# Xbee.net
KiCad netlist of a schematic drawn in Altium Designer
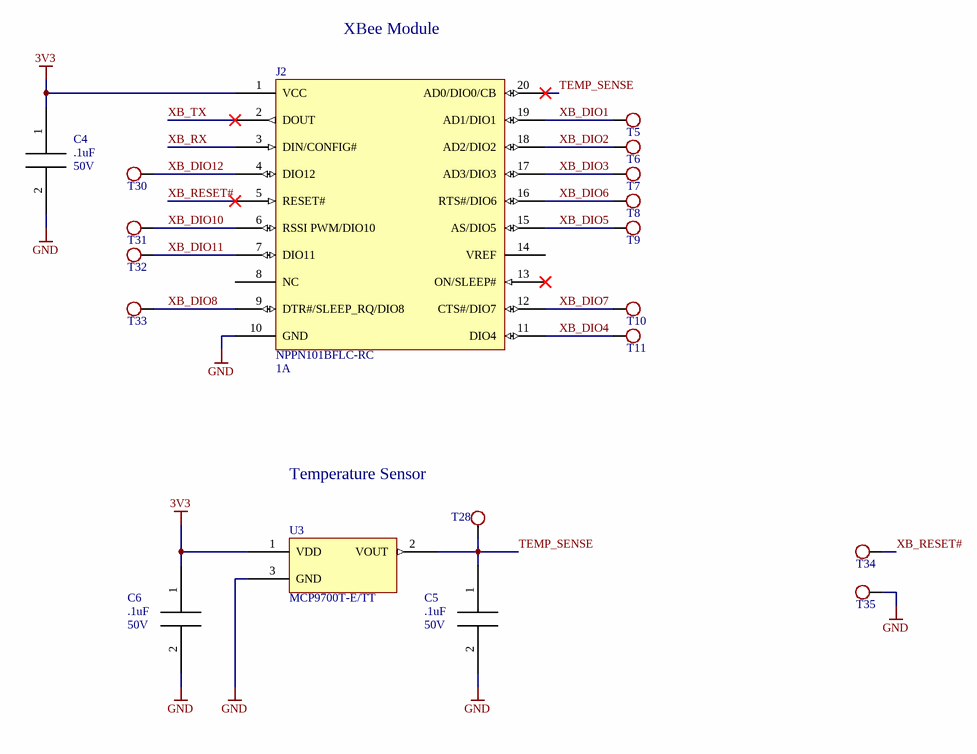
[diagram p0: Xbee.SchDoc]

(export (version "E")
  (design (tool "Eeschema 10.0.6"))
  (components
    (comp (ref "C4")
      (value ".1uF")
      (footprint "0603")
      (fields
        (field (name "PARTNUMBER") "C0603C104K5RACAUTO")
        (field (name "MANUFACTURER") "KEMET")
        (field (name "RATING") "50V")
      )
      (libsource (lib "*") (part "C_CAP_0603"))
    )
    (comp (ref "C5")
      (value ".1uF")
      (footprint "0603")
      (fields
        (field (name "PARTNUMBER") "C0603C104K5RACAUTO")
        (field (name "MANUFACTURER") "KEMET")
        (field (name "RATING") "50V")
      )
      (libsource (lib "*") (part "C_CAP_0603"))
    )
    (comp (ref "C6")
      (value ".1uF")
      (footprint "0603")
      (fields
        (field (name "PARTNUMBER") "C0603C104K5RACAUTO")
        (field (name "MANUFACTURER") "KEMET")
        (field (name "RATING") "50V")
      )
      (libsource (lib "*") (part "C_CAP_0603"))
    )
    (comp (ref "J2")
      (value "J_XBEE_NPPN101BFLC-RC")
      (footprint "NPPN101BFLC-RC")
      (fields
        (field (name "MANUFACTURER") "Sullins Connector Solutions")
        (field (name "PARTNUMBER") "NPPN101BFLC-RC")
        (field (name "RATING") "1A")
      )
      (libsource (lib "Hub") (part "J_XBEE_NPPN101BFLC-RC"))
    )
    (comp (ref "T5")
      (value "TESTPOINT")
      (footprint "TESTPOINT1MM")
      (libsource (lib "Hub") (part "T_TESTPOINT_TESTPOINT1MM"))
    )
    (comp (ref "T6")
      (value "TESTPOINT")
      (footprint "TESTPOINT1MM")
      (libsource (lib "Hub") (part "T_TESTPOINT_TESTPOINT1MM"))
    )
    (comp (ref "T7")
      (value "TESTPOINT")
      (footprint "TESTPOINT1MM")
      (libsource (lib "Hub") (part "T_TESTPOINT_TESTPOINT1MM"))
    )
    (comp (ref "T8")
      (value "TESTPOINT")
      (footprint "TESTPOINT1MM")
      (libsource (lib "Hub") (part "T_TESTPOINT_TESTPOINT1MM"))
    )
    (comp (ref "T9")
      (value "TESTPOINT")
      (footprint "TESTPOINT1MM")
      (libsource (lib "Hub") (part "T_TESTPOINT_TESTPOINT1MM"))
    )
    (comp (ref "T10")
      (value "TESTPOINT")
      (footprint "TESTPOINT1MM")
      (libsource (lib "Hub") (part "T_TESTPOINT_TESTPOINT1MM"))
    )
    (comp (ref "T11")
      (value "TESTPOINT")
      (footprint "TESTPOINT1MM")
      (libsource (lib "Hub") (part "T_TESTPOINT_TESTPOINT1MM"))
    )
    (comp (ref "T28")
      (value "TESTPOINT")
      (footprint "TESTPOINT1MM")
      (libsource (lib "Hub") (part "T_TESTPOINT_TESTPOINT1MM"))
    )
    (comp (ref "T30")
      (value "TESTPOINT")
      (footprint "TESTPOINT1MM")
      (libsource (lib "Hub") (part "T_TESTPOINT_TESTPOINT1MM"))
    )
    (comp (ref "T31")
      (value "TESTPOINT")
      (footprint "TESTPOINT1MM")
      (libsource (lib "Hub") (part "T_TESTPOINT_TESTPOINT1MM"))
    )
    (comp (ref "T32")
      (value "TESTPOINT")
      (footprint "TESTPOINT1MM")
      (libsource (lib "Hub") (part "T_TESTPOINT_TESTPOINT1MM"))
    )
    (comp (ref "T33")
      (value "TESTPOINT")
      (footprint "TESTPOINT1MM")
      (libsource (lib "Hub") (part "T_TESTPOINT_TESTPOINT1MM"))
    )
    (comp (ref "T34")
      (value "TESTPOINT")
      (footprint "TESTPOINT1MM")
      (libsource (lib "Hub") (part "T_TESTPOINT_TESTPOINT1MM"))
    )
    (comp (ref "T35")
      (value "TESTPOINT")
      (footprint "TESTPOINT1MM")
      (libsource (lib "Hub") (part "T_TESTPOINT_TESTPOINT1MM"))
    )
    (comp (ref "U3")
      (value "U_TEMPSENSE-AN_TO92")
      (footprint "TO92")
      (fields (field (name "MANUFACTURER") "Microchip") (field (name "PARTNUMBER") "MCP9700T-E/TT"))
      (libsource (lib "Hub") (part "U_TEMPSENSE-AN_TO92"))
    )
  )
  (nets
    (net (code "1") (name "/TEMP_SENSE") (class "Default")
      (node (ref "C5") (pin "1") (pintype "passive"))
      (node (ref "J2") (pin "20") (pinfunction "AD0/DIO0/CB_20") (pintype "bidirectional"))
      (node (ref "T28") (pin "1") (pintype "passive"))
      (node (ref "U3") (pin "2") (pinfunction "VOUT_2") (pintype "output"))
    )
    (net (code "2") (name "/XB_DIO1") (class "Default")
      (node (ref "J2") (pin "19") (pinfunction "AD1/DIO1_19") (pintype "bidirectional"))
      (node (ref "T5") (pin "1") (pintype "passive"))
    )
    (net (code "3") (name "/XB_DIO2") (class "Default")
      (node (ref "J2") (pin "18") (pinfunction "AD2/DIO2_18") (pintype "bidirectional"))
      (node (ref "T6") (pin "1") (pintype "passive"))
    )
    (net (code "4") (name "/XB_DIO3") (class "Default")
      (node (ref "J2") (pin "17") (pinfunction "AD3/DIO3_17") (pintype "bidirectional"))
      (node (ref "T7") (pin "1") (pintype "passive"))
    )
    (net (code "5") (name "/XB_DIO4") (class "Default")
      (node (ref "J2") (pin "11") (pinfunction "DIO4_11") (pintype "bidirectional"))
      (node (ref "T11") (pin "1") (pintype "passive"))
    )
    (net (code "6") (name "/XB_DIO5") (class "Default")
      (node (ref "J2") (pin "15") (pinfunction "AS/DIO5_15") (pintype "bidirectional"))
      (node (ref "T9") (pin "1") (pintype "passive"))
    )
    (net (code "7") (name "/XB_DIO6") (class "Default")
      (node (ref "J2") (pin "16") (pinfunction "RTS#/DIO6_16") (pintype "bidirectional"))
      (node (ref "T8") (pin "1") (pintype "passive"))
    )
    (net (code "8") (name "/XB_DIO7") (class "Default")
      (node (ref "J2") (pin "12") (pinfunction "CTS#/DIO7_12") (pintype "bidirectional"))
      (node (ref "T10") (pin "1") (pintype "passive"))
    )
    (net (code "9") (name "/XB_DIO8") (class "Default")
      (node (ref "J2") (pin "9") (pinfunction "DTR#/SLEEP_RQ/DIO8_9") (pintype "bidirectional"))
      (node (ref "T33") (pin "1") (pintype "passive"))
    )
    (net (code "10") (name "/XB_DIO10") (class "Default")
      (node (ref "J2") (pin "6") (pinfunction "RSSI_PWM/DIO10_6") (pintype "bidirectional"))
      (node (ref "T31") (pin "1") (pintype "passive"))
    )
    (net (code "11") (name "/XB_DIO11") (class "Default")
      (node (ref "J2") (pin "7") (pinfunction "DIO11_7") (pintype "bidirectional"))
      (node (ref "T32") (pin "1") (pintype "passive"))
    )
    (net (code "12") (name "/XB_DIO12") (class "Default")
      (node (ref "J2") (pin "4") (pinfunction "DIO12_4") (pintype "bidirectional"))
      (node (ref "T30") (pin "1") (pintype "passive"))
    )
    (net (code "13") (name "/XB_RESET#") (class "Default")
      (node (ref "J2") (pin "5") (pinfunction "RESET#_5") (pintype "input"))
      (node (ref "T34") (pin "1") (pintype "passive"))
    )
    (net (code "14") (name "/XB_RX") (class "Default")
      (node (ref "J2") (pin "3") (pinfunction "DIN/CONFIG#_3") (pintype "input"))
    )
    (net (code "15") (name "/XB_TX") (class "Default")
      (node (ref "J2") (pin "2") (pinfunction "DOUT_2") (pintype "output+no_connect"))
    )
    (net (code "16") (name "3V3") (class "Default")
      (node (ref "C4") (pin "1") (pintype "passive"))
      (node (ref "C6") (pin "1") (pintype "passive"))
      (node (ref "J2") (pin "1") (pinfunction "VCC_1") (pintype "power_in"))
      (node (ref "U3") (pin "1") (pinfunction "VDD_1") (pintype "power_in"))
    )
    (net (code "17") (name "GND") (class "Default")
      (node (ref "C4") (pin "2") (pintype "passive"))
      (node (ref "C5") (pin "2") (pintype "passive"))
      (node (ref "C6") (pin "2") (pintype "passive"))
      (node (ref "J2") (pin "10") (pinfunction "GND_10") (pintype "power_in"))
      (node (ref "T35") (pin "1") (pintype "passive"))
      (node (ref "U3") (pin "3") (pinfunction "GND_3") (pintype "power_in"))
    )
    (net (code "18") (name "unconnected-(J2-NC-Pad8)") (class "Default")
      (node (ref "J2") (pin "8") (pinfunction "NC_8") (pintype "passive"))
    )
    (net (code "19") (name "unconnected-(J2-ON{slash}SLEEP#-Pad13)") (class "Default")
      (node (ref "J2") (pin "13") (pinfunction "ON/SLEEP#_13") (pintype "input+no_connect"))
    )
    (net (code "20") (name "unconnected-(J2-VREF-Pad14)") (class "Default")
      (node (ref "J2") (pin "14") (pinfunction "VREF_14") (pintype "power_in"))
    )
  )
)
